# eps_bt2.net
KiCad netlist of a schematic drawn in Altium Designer
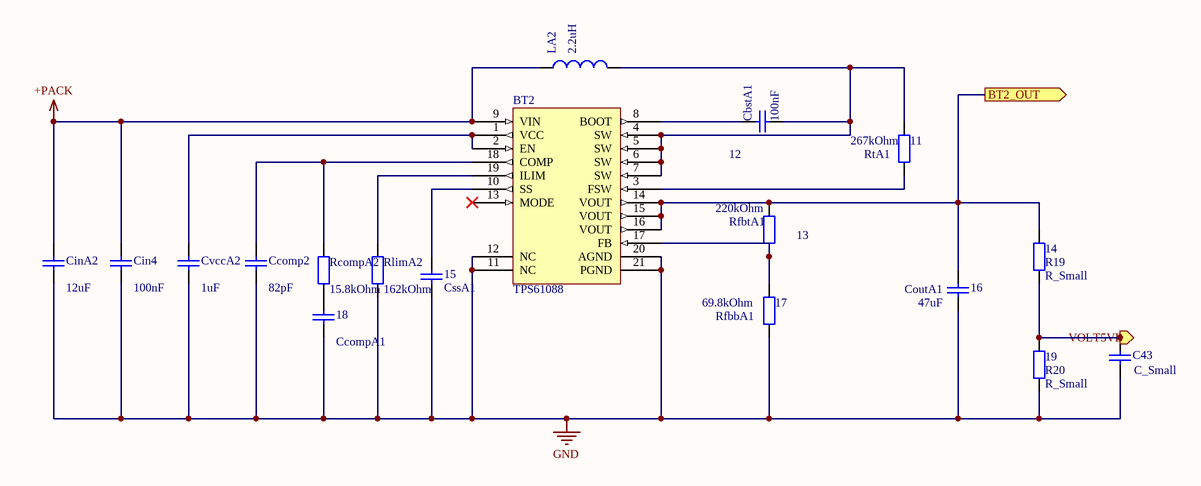
[diagram p0: eps_bt2.SchDoc]

(export (version "E")
  (design (tool "Eeschema 10.0.6"))
  (components
    (comp (ref "11")
      (value "RtA1")
      (footprint "1608[0603]")
      (description "Resistor")
      (fields (field (name "ALTIUM_VALUE") "267kOhm") (field (name "PUBLISHER") "Altium Limited"))
      (libsource (lib "") (part "Res2_1"))
    )
    (comp (ref "12")
      (value "CbstA1")
      (footprint "1608[0603]")
      (description "Capacitor")
      (fields (field (name "ALTIUM_VALUE") "100nF") (field (name "PUBLISHER") "Altium Limited"))
      (libsource (lib "Miscellaneous Devices") (part "Cap"))
    )
    (comp (ref "13")
      (value "RfbtA1")
      (footprint "1608[0603]")
      (description "Resistor")
      (fields (field (name "ALTIUM_VALUE") "220kOhm") (field (name "PUBLISHER") "Altium Limited"))
      (libsource (lib "Miscellaneous Devices") (part "Res2"))
    )
    (comp (ref "14")
      (value "R19")
      (footprint "1608[0603]")
      (description "Resistor")
      (fields (field (name "ALTIUM_VALUE") "R_Small") (field (name "PUBLISHER") "Altium Limited"))
      (libsource (lib "Miscellaneous Devices") (part "Res2"))
    )
    (comp (ref "15")
      (value "CssA1")
      (footprint "1608[0603]")
      (description "Capacitor")
      (fields (field (name "PUBLISHER") "Altium Limited"))
      (libsource (lib "Miscellaneous Devices") (part "Cap"))
    )
    (comp (ref "16")
      (value "CoutA1")
      (footprint "1608[0603]")
      (description "Capacitor")
      (fields (field (name "ALTIUM_VALUE") "47uF") (field (name "PUBLISHER") "Altium Limited"))
      (libsource (lib "Miscellaneous Devices") (part "Cap"))
    )
    (comp (ref "17")
      (value "RfbbA1")
      (footprint "1608[0603]")
      (description "Resistor")
      (fields (field (name "ALTIUM_VALUE") "69.8kOhm") (field (name "PUBLISHER") "Altium Limited"))
      (libsource (lib "Miscellaneous Devices") (part "Res2"))
    )
    (comp (ref "18")
      (value "CcompA1")
      (footprint "1608[0603]")
      (description "Capacitor")
      (fields (field (name "PUBLISHER") "Altium Limited"))
      (libsource (lib "Miscellaneous Devices") (part "Cap"))
    )
    (comp (ref "19")
      (value "R20")
      (footprint "1608[0603]")
      (description "Resistor")
      (fields (field (name "ALTIUM_VALUE") "R_Small") (field (name "PUBLISHER") "Altium Limited"))
      (libsource (lib "Miscellaneous Devices") (part "Res2"))
    )
    (comp (ref "BT2")
      (value "TPS61088")
      (footprint "QFN50P450X350X100-21N")
      (description "Boost converter")
      (libsource (lib "heron-general") (part "TPS61088"))
    )
    (comp (ref "C43")
      (value "C_Small")
      (footprint "1608[0603]")
      (description "Capacitor")
      (fields (field (name "PUBLISHER") "Altium Limited"))
      (libsource (lib "Miscellaneous Devices") (part "Cap"))
    )
    (comp (ref "Ccomp2")
      (value "82pF")
      (footprint "1608[0603]")
      (description "Capacitor")
      (fields (field (name "PUBLISHER") "Altium Limited"))
      (libsource (lib "Miscellaneous Devices") (part "Cap"))
    )
    (comp (ref "Cin4")
      (value "100nF")
      (footprint "1608[0603]")
      (description "Capacitor")
      (fields (field (name "PUBLISHER") "Altium Limited"))
      (libsource (lib "Miscellaneous Devices") (part "Cap"))
    )
    (comp (ref "CinA2")
      (value "12uF")
      (footprint "1608[0603]")
      (description "Capacitor")
      (fields (field (name "PUBLISHER") "Altium Limited"))
      (libsource (lib "Miscellaneous Devices") (part "Cap"))
    )
    (comp (ref "CvccA2")
      (value "1uF")
      (footprint "1608[0603]")
      (description "Capacitor")
      (fields (field (name "PUBLISHER") "Altium Limited"))
      (libsource (lib "Miscellaneous Devices") (part "Cap"))
    )
    (comp (ref "LA2")
      (value "2.2uH")
      (footprint "1608[0603]")
      (description "Inductor")
      (fields (field (name "PUBLISHER") "Altium Limited"))
      (libsource (lib "Miscellaneous Devices") (part "Inductor"))
    )
    (comp (ref "RcompA2")
      (value "15.8kOhm")
      (footprint "1608[0603]")
      (description "Resistor")
      (fields (field (name "PUBLISHER") "Altium Limited"))
      (libsource (lib "Miscellaneous Devices") (part "Res2"))
    )
    (comp (ref "RlimA2")
      (value "162kOhm")
      (footprint "1608[0603]")
      (description "Resistor")
      (fields (field (name "PUBLISHER") "Altium Limited"))
      (libsource (lib "Miscellaneous Devices") (part "Res2"))
    )
  )
  (nets
    (net (code "1") (name "+PACK") (class "Default")
      (node (ref "BT2") (pin "9") (pinfunction "VIN_9") (pintype "input"))
      (node (ref "Cin4") (pin "2") (pinfunction "2_2") (pintype "passive"))
      (node (ref "CinA2") (pin "2") (pinfunction "2_2") (pintype "passive"))
      (node (ref "LA2") (pin "1") (pinfunction "1_1") (pintype "passive"))
    )
    (net (code "2") (name "/BT2_OUT") (class "Default")
      (node (ref "13") (pin "2") (pinfunction "2_2") (pintype "passive"))
      (node (ref "14") (pin "2") (pinfunction "2_2") (pintype "passive"))
      (node (ref "16") (pin "2") (pinfunction "2_2") (pintype "passive"))
      (node (ref "BT2") (pin "14") (pinfunction "VOUT_14") (pintype "output"))
      (node (ref "BT2") (pin "15") (pinfunction "VOUT_15") (pintype "output"))
      (node (ref "BT2") (pin "16") (pinfunction "VOUT_16") (pintype "output"))
    )
    (net (code "3") (name "/VOLT5VB") (class "Default")
      (node (ref "14") (pin "1") (pinfunction "1_1") (pintype "passive"))
      (node (ref "19") (pin "2") (pinfunction "2_2") (pintype "passive"))
      (node (ref "C43") (pin "1") (pinfunction "1_1") (pintype "passive"))
    )
    (net (code "4") (name "GND") (class "Default")
      (node (ref "15") (pin "1") (pinfunction "1_1") (pintype "passive"))
      (node (ref "16") (pin "1") (pinfunction "1_1") (pintype "passive"))
      (node (ref "17") (pin "1") (pinfunction "1_1") (pintype "passive"))
      (node (ref "18") (pin "1") (pinfunction "1_1") (pintype "passive"))
      (node (ref "19") (pin "1") (pinfunction "1_1") (pintype "passive"))
      (node (ref "BT2") (pin "11") (pinfunction "NC_11") (pintype "passive"))
      (node (ref "BT2") (pin "12") (pinfunction "NC_12") (pintype "passive"))
      (node (ref "BT2") (pin "20") (pinfunction "AGND_20") (pintype "power_in"))
      (node (ref "BT2") (pin "21") (pinfunction "PGND_21") (pintype "power_in"))
      (node (ref "C43") (pin "2") (pinfunction "2_2") (pintype "passive"))
      (node (ref "Ccomp2") (pin "1") (pinfunction "1_1") (pintype "passive"))
      (node (ref "Cin4") (pin "1") (pinfunction "1_1") (pintype "passive"))
      (node (ref "CinA2") (pin "1") (pinfunction "1_1") (pintype "passive"))
      (node (ref "CvccA2") (pin "1") (pinfunction "1_1") (pintype "passive"))
      (node (ref "RlimA2") (pin "1") (pinfunction "1_1") (pintype "passive"))
    )
    (net (code "5") (name "Net-(11-Pad1)") (class "Default")
      (node (ref "11") (pin "1") (pinfunction "1_1") (pintype "passive"))
      (node (ref "12") (pin "1") (pinfunction "1_1") (pintype "passive"))
      (node (ref "BT2") (pin "4") (pinfunction "SW_4") (pintype "input"))
      (node (ref "BT2") (pin "5") (pinfunction "SW_5") (pintype "input"))
      (node (ref "BT2") (pin "6") (pinfunction "SW_6") (pintype "input"))
      (node (ref "BT2") (pin "7") (pinfunction "SW_7") (pintype "input"))
      (node (ref "LA2") (pin "2") (pinfunction "2_2") (pintype "passive"))
    )
    (net (code "6") (name "Net-(18-Pad2)") (class "Default")
      (node (ref "18") (pin "2") (pinfunction "2_2") (pintype "passive"))
      (node (ref "RcompA2") (pin "1") (pinfunction "1_1") (pintype "passive"))
    )
    (net (code "7") (name "Net-(BT2-BOOT)") (class "Default")
      (node (ref "12") (pin "2") (pinfunction "2_2") (pintype "passive"))
      (node (ref "BT2") (pin "8") (pinfunction "BOOT_8") (pintype "output"))
    )
    (net (code "8") (name "Net-(BT2-COMP)") (class "Default")
      (node (ref "BT2") (pin "18") (pinfunction "COMP_18") (pintype "output"))
      (node (ref "Ccomp2") (pin "2") (pinfunction "2_2") (pintype "passive"))
      (node (ref "RcompA2") (pin "2") (pinfunction "2_2") (pintype "passive"))
    )
    (net (code "9") (name "Net-(BT2-EN)") (class "Default")
      (node (ref "BT2") (pin "1") (pinfunction "VCC_1") (pintype "output"))
      (node (ref "BT2") (pin "2") (pinfunction "EN_2") (pintype "input"))
      (node (ref "CvccA2") (pin "2") (pinfunction "2_2") (pintype "passive"))
    )
    (net (code "10") (name "Net-(BT2-FB)") (class "Default")
      (node (ref "13") (pin "1") (pinfunction "1_1") (pintype "passive"))
      (node (ref "17") (pin "2") (pinfunction "2_2") (pintype "passive"))
      (node (ref "BT2") (pin "17") (pinfunction "FB_17") (pintype "input"))
    )
    (net (code "11") (name "Net-(BT2-FSW)") (class "Default")
      (node (ref "11") (pin "2") (pinfunction "2_2") (pintype "passive"))
      (node (ref "BT2") (pin "3") (pinfunction "FSW_3") (pintype "input"))
    )
    (net (code "12") (name "Net-(BT2-ILIM)") (class "Default")
      (node (ref "BT2") (pin "19") (pinfunction "ILIM_19") (pintype "output"))
      (node (ref "RlimA2") (pin "2") (pinfunction "2_2") (pintype "passive"))
    )
    (net (code "13") (name "Net-(BT2-SS)") (class "Default")
      (node (ref "15") (pin "2") (pinfunction "2_2") (pintype "passive"))
      (node (ref "BT2") (pin "10") (pinfunction "SS_10") (pintype "output"))
    )
    (net (code "14") (name "unconnected-(BT2-MODE-Pad13)") (class "Default")
      (node (ref "BT2") (pin "13") (pinfunction "MODE_13") (pintype "input+no_connect"))
    )
  )
)
